# M503X.net
KiCad netlist of a schematic drawn in EAGLE
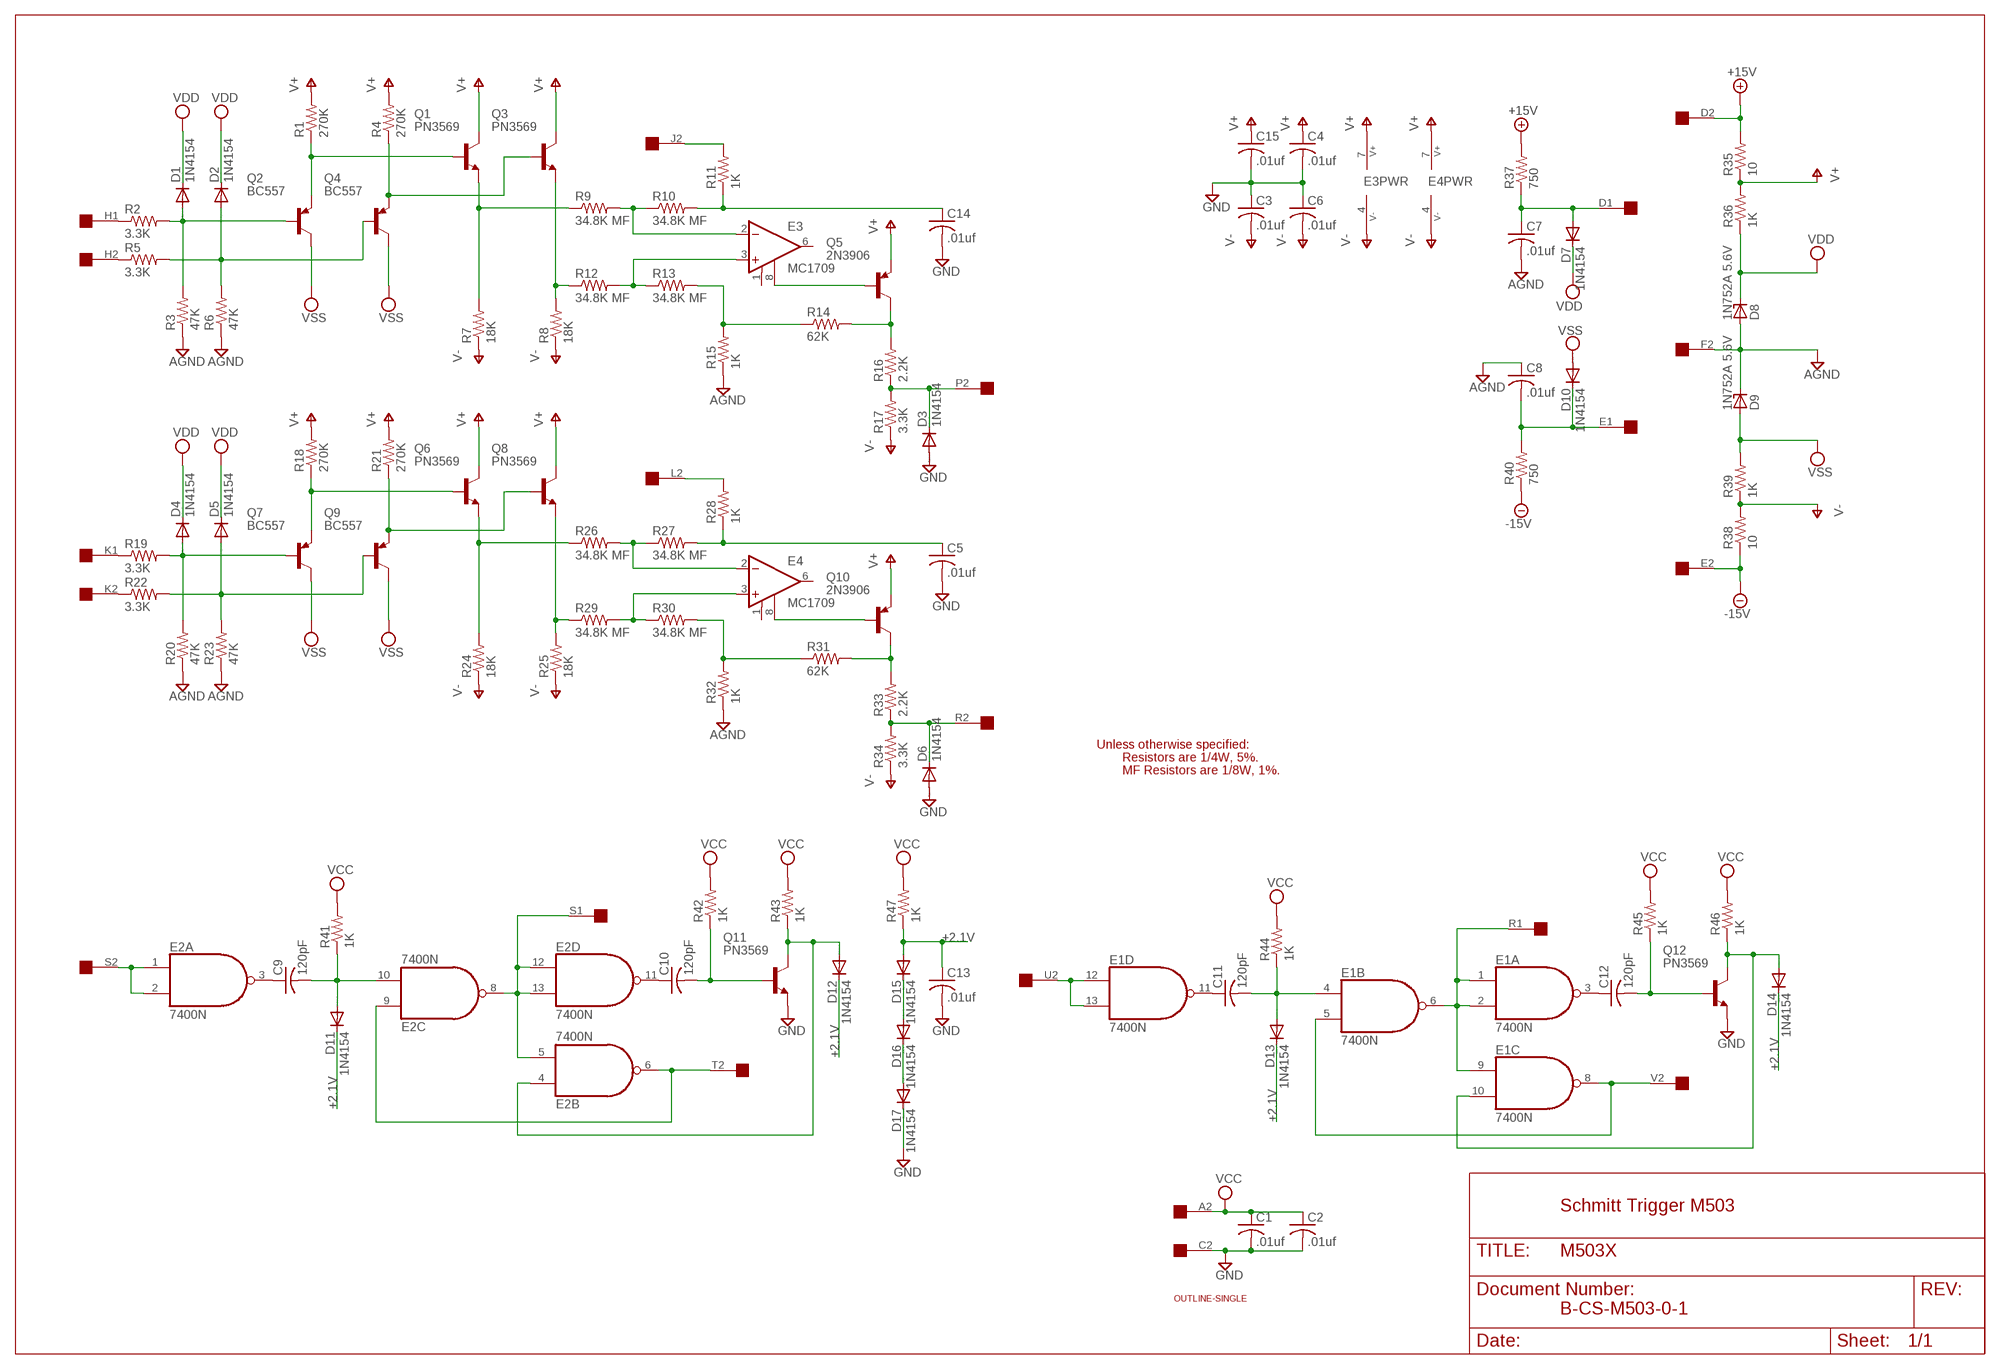
[diagram p0: schematic, sheet 1]

(export (version "E")
  (design (tool "Eeschema 10.0.6"))
  (components
    (comp (ref "C1")
      (value ".01uf")
      (footprint "eagle-import:C075-032X103")
      (libsource (lib "eagle-import") (part "C-US075-032X103"))
    )
    (comp (ref "C2")
      (value ".01uf")
      (footprint "eagle-import:C075-032X103")
      (libsource (lib "eagle-import") (part "C-US075-032X103"))
    )
    (comp (ref "C3")
      (value ".01uf")
      (footprint "eagle-import:C050-025X075")
      (libsource (lib "eagle-import") (part "C-US050-025X075"))
    )
    (comp (ref "C4")
      (value ".01uf")
      (footprint "eagle-import:C050-025X075")
      (libsource (lib "eagle-import") (part "C-US050-025X075"))
    )
    (comp (ref "C5")
      (value ".01uf")
      (footprint "eagle-import:C050-025X075")
      (libsource (lib "eagle-import") (part "C-US050-025X075"))
    )
    (comp (ref "C6")
      (value ".01uf")
      (footprint "eagle-import:C050-025X075")
      (libsource (lib "eagle-import") (part "C-US050-025X075"))
    )
    (comp (ref "C7")
      (value ".01uf")
      (footprint "eagle-import:C050-025X075")
      (libsource (lib "eagle-import") (part "C-US050-025X075"))
    )
    (comp (ref "C8")
      (value ".01uf")
      (footprint "eagle-import:C050-025X075")
      (libsource (lib "eagle-import") (part "C-US050-025X075"))
    )
    (comp (ref "C9")
      (value "120pF")
      (footprint "eagle-import:C050-025X075")
      (libsource (lib "eagle-import") (part "C-US050-025X075"))
    )
    (comp (ref "C10")
      (value "120pF")
      (footprint "eagle-import:C050-025X075")
      (libsource (lib "eagle-import") (part "C-US050-025X075"))
    )
    (comp (ref "C11")
      (value "120pF")
      (footprint "eagle-import:C050-025X075")
      (libsource (lib "eagle-import") (part "C-US050-025X075"))
    )
    (comp (ref "C12")
      (value "120pF")
      (footprint "eagle-import:C050-025X075")
      (libsource (lib "eagle-import") (part "C-US050-025X075"))
    )
    (comp (ref "C13")
      (value ".01uf")
      (footprint "eagle-import:C050-025X075")
      (libsource (lib "eagle-import") (part "C-US050-025X075"))
    )
    (comp (ref "C14")
      (value ".01uf")
      (footprint "eagle-import:C050-025X075")
      (libsource (lib "eagle-import") (part "C-US050-025X075"))
    )
    (comp (ref "C15")
      (value ".01uf")
      (footprint "eagle-import:C050-025X075")
      (libsource (lib "eagle-import") (part "C-US050-025X075"))
    )
    (comp (ref "D1")
      (value "1N4154")
      (footprint "eagle-import:DO35-10")
      (libsource (lib "eagle-import") (part "1N4148DO35-10"))
    )
    (comp (ref "D2")
      (value "1N4154")
      (footprint "eagle-import:DO35-10")
      (libsource (lib "eagle-import") (part "1N4148DO35-10"))
    )
    (comp (ref "D3")
      (value "1N4154")
      (footprint "eagle-import:DO35-10")
      (libsource (lib "eagle-import") (part "1N4148DO35-10"))
    )
    (comp (ref "D4")
      (value "1N4154")
      (footprint "eagle-import:DO35-10")
      (libsource (lib "eagle-import") (part "1N4148DO35-10"))
    )
    (comp (ref "D5")
      (value "1N4154")
      (footprint "eagle-import:DO35-10")
      (libsource (lib "eagle-import") (part "1N4148DO35-10"))
    )
    (comp (ref "D6")
      (value "1N4154")
      (footprint "eagle-import:DO35-10")
      (libsource (lib "eagle-import") (part "1N4148DO35-10"))
    )
    (comp (ref "D7")
      (value "1N4154")
      (footprint "eagle-import:DO35-10")
      (libsource (lib "eagle-import") (part "1N4148DO35-10"))
    )
    (comp (ref "D8")
      (value "1N752A 5.6V")
      (footprint "eagle-import:DO35Z10")
      (libsource (lib "eagle-import") (part "ZENER-DIODEDO35Z10"))
    )
    (comp (ref "D9")
      (value "1N752A 5.6V")
      (footprint "eagle-import:DO35Z10")
      (libsource (lib "eagle-import") (part "ZENER-DIODEDO35Z10"))
    )
    (comp (ref "D10")
      (value "1N4154")
      (footprint "eagle-import:DO35-10")
      (libsource (lib "eagle-import") (part "1N4148DO35-10"))
    )
    (comp (ref "D11")
      (value "1N4154")
      (footprint "eagle-import:DO35-10")
      (libsource (lib "eagle-import") (part "1N4148DO35-10"))
    )
    (comp (ref "D12")
      (value "1N4154")
      (footprint "eagle-import:DO35-10")
      (libsource (lib "eagle-import") (part "1N4148DO35-10"))
    )
    (comp (ref "D13")
      (value "1N4154")
      (footprint "eagle-import:DO35-10")
      (libsource (lib "eagle-import") (part "1N4148DO35-10"))
    )
    (comp (ref "D14")
      (value "1N4154")
      (footprint "eagle-import:DO35-10")
      (libsource (lib "eagle-import") (part "1N4148DO35-10"))
    )
    (comp (ref "D15")
      (value "1N4154")
      (footprint "eagle-import:DO35-10")
      (libsource (lib "eagle-import") (part "1N4148DO35-10"))
    )
    (comp (ref "D16")
      (value "1N4154")
      (footprint "eagle-import:DO35-10")
      (libsource (lib "eagle-import") (part "1N4148DO35-10"))
    )
    (comp (ref "D17")
      (value "1N4154")
      (footprint "eagle-import:DO35-10")
      (libsource (lib "eagle-import") (part "1N4148DO35-10"))
    )
    (comp (ref "E1")
      (value "7400N")
      (footprint "eagle-import:DIL14")
      (libsource (lib "eagle-import") (part "7400N"))
    )
    (comp (ref "E2")
      (value "7400N")
      (footprint "eagle-import:DIL14")
      (libsource (lib "eagle-import") (part "7400N"))
    )
    (comp (ref "E3")
      (value "MC1709")
      (footprint "eagle-import:TO99C")
      (libsource (lib "eagle-import") (part "LM301C"))
    )
    (comp (ref "E4")
      (value "MC1709")
      (footprint "eagle-import:TO99B")
      (libsource (lib "eagle-import") (part "LM301B"))
    )
    (comp (ref "Q1")
      (value "PN3569")
      (footprint "eagle-import:TO39")
      (libsource (lib "eagle-import") (part "2N3019"))
    )
    (comp (ref "Q2")
      (value "BC557")
      (footprint "eagle-import:TO39")
      (libsource (lib "eagle-import") (part "2N2904"))
    )
    (comp (ref "Q3")
      (value "PN3569")
      (footprint "eagle-import:TO39")
      (libsource (lib "eagle-import") (part "2N3019"))
    )
    (comp (ref "Q4")
      (value "BC557")
      (footprint "eagle-import:TO39")
      (libsource (lib "eagle-import") (part "2N2904"))
    )
    (comp (ref "Q5")
      (value "2N3906")
      (footprint "eagle-import:TO39")
      (libsource (lib "eagle-import") (part "2N2904"))
    )
    (comp (ref "Q6")
      (value "PN3569")
      (footprint "eagle-import:TO39")
      (libsource (lib "eagle-import") (part "2N3019"))
    )
    (comp (ref "Q7")
      (value "BC557")
      (footprint "eagle-import:TO39")
      (libsource (lib "eagle-import") (part "2N2904"))
    )
    (comp (ref "Q8")
      (value "PN3569")
      (footprint "eagle-import:TO39")
      (libsource (lib "eagle-import") (part "2N3019"))
    )
    (comp (ref "Q9")
      (value "BC557")
      (footprint "eagle-import:TO39")
      (libsource (lib "eagle-import") (part "2N2904"))
    )
    (comp (ref "Q10")
      (value "2N3906")
      (footprint "eagle-import:TO39")
      (libsource (lib "eagle-import") (part "2N2904"))
    )
    (comp (ref "Q11")
      (value "PN3569")
      (footprint "eagle-import:TO39")
      (libsource (lib "eagle-import") (part "2N3019"))
    )
    (comp (ref "Q12")
      (value "PN3569")
      (footprint "eagle-import:TO39")
      (libsource (lib "eagle-import") (part "2N3019"))
    )
    (comp (ref "R1")
      (value "270K")
      (footprint "eagle-import:0207_10")
      (libsource (lib "eagle-import") (part "R-US_0207/10"))
    )
    (comp (ref "R2")
      (value "3.3K")
      (footprint "eagle-import:0207_10")
      (libsource (lib "eagle-import") (part "R-US_0207/10"))
    )
    (comp (ref "R3")
      (value "47K")
      (footprint "eagle-import:0207_10")
      (libsource (lib "eagle-import") (part "R-US_0207/10"))
    )
    (comp (ref "R4")
      (value "270K")
      (footprint "eagle-import:0207_10")
      (libsource (lib "eagle-import") (part "R-US_0207/10"))
    )
    (comp (ref "R5")
      (value "3.3K")
      (footprint "eagle-import:0207_10")
      (libsource (lib "eagle-import") (part "R-US_0207/10"))
    )
    (comp (ref "R6")
      (value "47K")
      (footprint "eagle-import:0207_10")
      (libsource (lib "eagle-import") (part "R-US_0207/10"))
    )
    (comp (ref "R7")
      (value "18K")
      (footprint "eagle-import:0207_10")
      (libsource (lib "eagle-import") (part "R-US_0207/10"))
    )
    (comp (ref "R8")
      (value "18K")
      (footprint "eagle-import:0207_10")
      (libsource (lib "eagle-import") (part "R-US_0207/10"))
    )
    (comp (ref "R9")
      (value "34.8K MF")
      (footprint "eagle-import:0207_10")
      (libsource (lib "eagle-import") (part "R-US_0207/10"))
    )
    (comp (ref "R10")
      (value "34.8K MF")
      (footprint "eagle-import:0207_10")
      (libsource (lib "eagle-import") (part "R-US_0207/10"))
    )
    (comp (ref "R11")
      (value "1K")
      (footprint "eagle-import:0207_10")
      (libsource (lib "eagle-import") (part "R-US_0207/10"))
    )
    (comp (ref "R12")
      (value "34.8K MF")
      (footprint "eagle-import:0207_10")
      (libsource (lib "eagle-import") (part "R-US_0207/10"))
    )
    (comp (ref "R13")
      (value "34.8K MF")
      (footprint "eagle-import:0207_10")
      (libsource (lib "eagle-import") (part "R-US_0207/10"))
    )
    (comp (ref "R14")
      (value "62K")
      (footprint "eagle-import:0207_10")
      (libsource (lib "eagle-import") (part "R-US_0207/10"))
    )
    (comp (ref "R15")
      (value "1K")
      (footprint "eagle-import:0207_10")
      (libsource (lib "eagle-import") (part "R-US_0207/10"))
    )
    (comp (ref "R16")
      (value "2.2K")
      (footprint "eagle-import:0207_10")
      (libsource (lib "eagle-import") (part "R-US_0207/10"))
    )
    (comp (ref "R17")
      (value "3.3K")
      (footprint "eagle-import:0207_10")
      (libsource (lib "eagle-import") (part "R-US_0207/10"))
    )
    (comp (ref "R18")
      (value "270K")
      (footprint "eagle-import:0207_10")
      (libsource (lib "eagle-import") (part "R-US_0207/10"))
    )
    (comp (ref "R19")
      (value "3.3K")
      (footprint "eagle-import:0207_10")
      (libsource (lib "eagle-import") (part "R-US_0207/10"))
    )
    (comp (ref "R20")
      (value "47K")
      (footprint "eagle-import:0207_10")
      (libsource (lib "eagle-import") (part "R-US_0207/10"))
    )
    (comp (ref "R21")
      (value "270K")
      (footprint "eagle-import:0207_10")
      (libsource (lib "eagle-import") (part "R-US_0207/10"))
    )
    (comp (ref "R22")
      (value "3.3K")
      (footprint "eagle-import:0207_10")
      (libsource (lib "eagle-import") (part "R-US_0207/10"))
    )
    (comp (ref "R23")
      (value "47K")
      (footprint "eagle-import:0207_10")
      (libsource (lib "eagle-import") (part "R-US_0207/10"))
    )
    (comp (ref "R24")
      (value "18K")
      (footprint "eagle-import:0207_10")
      (libsource (lib "eagle-import") (part "R-US_0207/10"))
    )
    (comp (ref "R25")
      (value "18K")
      (footprint "eagle-import:0207_10")
      (libsource (lib "eagle-import") (part "R-US_0207/10"))
    )
    (comp (ref "R26")
      (value "34.8K MF")
      (footprint "eagle-import:0207_10")
      (libsource (lib "eagle-import") (part "R-US_0207/10"))
    )
    (comp (ref "R27")
      (value "34.8K MF")
      (footprint "eagle-import:0207_10")
      (libsource (lib "eagle-import") (part "R-US_0207/10"))
    )
    (comp (ref "R28")
      (value "1K")
      (footprint "eagle-import:0207_10")
      (libsource (lib "eagle-import") (part "R-US_0207/10"))
    )
    (comp (ref "R29")
      (value "34.8K MF")
      (footprint "eagle-import:0207_10")
      (libsource (lib "eagle-import") (part "R-US_0207/10"))
    )
    (comp (ref "R30")
      (value "34.8K MF")
      (footprint "eagle-import:0207_10")
      (libsource (lib "eagle-import") (part "R-US_0207/10"))
    )
    (comp (ref "R31")
      (value "62K")
      (footprint "eagle-import:0207_10")
      (libsource (lib "eagle-import") (part "R-US_0207/10"))
    )
    (comp (ref "R32")
      (value "1K")
      (footprint "eagle-import:0207_10")
      (libsource (lib "eagle-import") (part "R-US_0207/10"))
    )
    (comp (ref "R33")
      (value "2.2K")
      (footprint "eagle-import:0207_10")
      (libsource (lib "eagle-import") (part "R-US_0207/10"))
    )
    (comp (ref "R34")
      (value "3.3K")
      (footprint "eagle-import:0207_10")
      (libsource (lib "eagle-import") (part "R-US_0207/10"))
    )
    (comp (ref "R35")
      (value "10")
      (footprint "eagle-import:0207_10")
      (libsource (lib "eagle-import") (part "R-US_0207/10"))
    )
    (comp (ref "R36")
      (value "1K")
      (footprint "eagle-import:0207_10")
      (libsource (lib "eagle-import") (part "R-US_0207/10"))
    )
    (comp (ref "R37")
      (value "750")
      (footprint "eagle-import:0207_10")
      (libsource (lib "eagle-import") (part "R-US_0207/10"))
    )
    (comp (ref "R38")
      (value "10")
      (footprint "eagle-import:0207_10")
      (libsource (lib "eagle-import") (part "R-US_0207/10"))
    )
    (comp (ref "R39")
      (value "1K")
      (footprint "eagle-import:0207_10")
      (libsource (lib "eagle-import") (part "R-US_0207/10"))
    )
    (comp (ref "R40")
      (value "750")
      (footprint "eagle-import:0207_10")
      (libsource (lib "eagle-import") (part "R-US_0207/10"))
    )
    (comp (ref "R41")
      (value "1K")
      (footprint "eagle-import:0207_10")
      (libsource (lib "eagle-import") (part "R-US_0207/10"))
    )
    (comp (ref "R42")
      (value "1K")
      (footprint "eagle-import:0207_10")
      (libsource (lib "eagle-import") (part "R-US_0207/10"))
    )
    (comp (ref "R43")
      (value "1K")
      (footprint "eagle-import:0207_10")
      (libsource (lib "eagle-import") (part "R-US_0207/10"))
    )
    (comp (ref "R44")
      (value "1K")
      (footprint "eagle-import:0207_10")
      (libsource (lib "eagle-import") (part "R-US_0207/10"))
    )
    (comp (ref "R45")
      (value "1K")
      (footprint "eagle-import:0207_10")
      (libsource (lib "eagle-import") (part "R-US_0207/10"))
    )
    (comp (ref "R46")
      (value "1K")
      (footprint "eagle-import:0207_10")
      (libsource (lib "eagle-import") (part "R-US_0207/10"))
    )
    (comp (ref "R47")
      (value "1K")
      (footprint "eagle-import:0207_10")
      (libsource (lib "eagle-import") (part "R-US_0207/10"))
    )
    (comp (ref "U$2")
      (value "SINGLE")
      (footprint "eagle-import:EDGE-CON2")
      (libsource (lib "eagle-import") (part "SINGLE"))
    )
    (comp (ref "U$4")
      (value "OUTLINE-SINGLE")
      (footprint "eagle-import:SINGLE")
      (libsource (lib "eagle-import") (part "OUTLINE-SINGLE"))
    )
  )
  (nets
    (net (code "1") (name "+15V") (class "Default")
      (node (ref "R35") (pin "2") (pinfunction "2_2") (pintype "passive"))
      (node (ref "R37") (pin "2") (pinfunction "2_2") (pintype "passive"))
      (node (ref "U$2") (pin "D2") (pinfunction "1_D2") (pintype "bidirectional"))
    )
    (net (code "2") (name "-15V") (class "Default")
      (node (ref "R38") (pin "1") (pinfunction "1_1") (pintype "passive"))
      (node (ref "R40") (pin "1") (pinfunction "1_1") (pintype "passive"))
      (node (ref "U$2") (pin "E2") (pinfunction "1_E2") (pintype "bidirectional"))
    )
    (net (code "3") (name "/+2.1V") (class "Default")
      (node (ref "C13") (pin "1") (pinfunction "1_1") (pintype "passive"))
      (node (ref "D11") (pin "C") (pinfunction "C_C") (pintype "passive"))
      (node (ref "D12") (pin "C") (pinfunction "C_C") (pintype "passive"))
      (node (ref "D13") (pin "C") (pinfunction "C_C") (pintype "passive"))
      (node (ref "D14") (pin "C") (pinfunction "C_C") (pintype "passive"))
      (node (ref "D15") (pin "A") (pinfunction "A_A") (pintype "passive"))
      (node (ref "R47") (pin "1") (pinfunction "1_1") (pintype "passive"))
    )
    (net (code "4") (name "AGND") (class "Default")
      (node (ref "C7") (pin "2") (pinfunction "2_2") (pintype "passive"))
      (node (ref "C8") (pin "1") (pinfunction "1_1") (pintype "passive"))
      (node (ref "D8") (pin "A") (pinfunction "A_A") (pintype "passive"))
      (node (ref "D9") (pin "C") (pinfunction "C_C") (pintype "passive"))
      (node (ref "R15") (pin "1") (pinfunction "1_1") (pintype "passive"))
      (node (ref "R20") (pin "1") (pinfunction "1_1") (pintype "passive"))
      (node (ref "R23") (pin "1") (pinfunction "1_1") (pintype "passive"))
      (node (ref "R3") (pin "1") (pinfunction "1_1") (pintype "passive"))
      (node (ref "R32") (pin "1") (pinfunction "1_1") (pintype "passive"))
      (node (ref "R6") (pin "1") (pinfunction "1_1") (pintype "passive"))
      (node (ref "U$2") (pin "F2") (pinfunction "1_F2") (pintype "bidirectional"))
    )
    (net (code "5") (name "GND") (class "Default")
      (node (ref "C1") (pin "2") (pinfunction "2_2") (pintype "passive"))
      (node (ref "C13") (pin "2") (pinfunction "2_2") (pintype "passive"))
      (node (ref "C14") (pin "2") (pinfunction "2_2") (pintype "passive"))
      (node (ref "C15") (pin "2") (pinfunction "2_2") (pintype "passive"))
      (node (ref "C2") (pin "2") (pinfunction "2_2") (pintype "passive"))
      (node (ref "C3") (pin "1") (pinfunction "1_1") (pintype "passive"))
      (node (ref "C4") (pin "2") (pinfunction "2_2") (pintype "passive"))
      (node (ref "C5") (pin "2") (pinfunction "2_2") (pintype "passive"))
      (node (ref "C6") (pin "1") (pinfunction "1_1") (pintype "passive"))
      (node (ref "D17") (pin "C") (pinfunction "C_C") (pintype "passive"))
      (node (ref "D3") (pin "A") (pinfunction "A_A") (pintype "passive"))
      (node (ref "D6") (pin "A") (pinfunction "A_A") (pintype "passive"))
      (node (ref "Q11") (pin "1") (pinfunction "E_1") (pintype "passive"))
      (node (ref "Q12") (pin "1") (pinfunction "E_1") (pintype "passive"))
      (node (ref "U$2") (pin "C2") (pinfunction "1_C2") (pintype "bidirectional"))
    )
    (net (code "6") (name "Net-(C5-Pad1)") (class "Default")
      (node (ref "C5") (pin "1") (pinfunction "1_1") (pintype "passive"))
      (node (ref "R27") (pin "2") (pinfunction "2_2") (pintype "passive"))
      (node (ref "R28") (pin "1") (pinfunction "1_1") (pintype "passive"))
    )
    (net (code "7") (name "Net-(C14-Pad1)") (class "Default")
      (node (ref "C14") (pin "1") (pinfunction "1_1") (pintype "passive"))
      (node (ref "R10") (pin "2") (pinfunction "2_2") (pintype "passive"))
      (node (ref "R11") (pin "1") (pinfunction "1_1") (pintype "passive"))
    )
    (net (code "8") (name "Net-(D15-PadC)") (class "Default")
      (node (ref "D15") (pin "C") (pinfunction "C_C") (pintype "passive"))
      (node (ref "D16") (pin "A") (pinfunction "A_A") (pintype "passive"))
    )
    (net (code "9") (name "Net-(D16-PadC)") (class "Default")
      (node (ref "D16") (pin "C") (pinfunction "C_C") (pintype "passive"))
      (node (ref "D17") (pin "A") (pinfunction "A_A") (pintype "passive"))
    )
    (net (code "10") (name "Net-(E1A-I0)") (class "Default")
      (node (ref "E1") (pin "1") (pinfunction "I0_1") (pintype "input"))
      (node (ref "E1") (pin "2") (pinfunction "I1_2") (pintype "input"))
      (node (ref "E1") (pin "6") (pinfunction "O_6") (pintype "output"))
      (node (ref "E1") (pin "9") (pinfunction "I0_9") (pintype "input"))
      (node (ref "U$2") (pin "R1") (pinfunction "1_R1") (pintype "bidirectional"))
    )
    (net (code "11") (name "Net-(E1A-O)") (class "Default")
      (node (ref "C12") (pin "1") (pinfunction "1_1") (pintype "passive"))
      (node (ref "E1") (pin "3") (pinfunction "O_3") (pintype "output"))
    )
    (net (code "12") (name "Net-(E1B-I0)") (class "Default")
      (node (ref "C11") (pin "2") (pinfunction "2_2") (pintype "passive"))
      (node (ref "D13") (pin "A") (pinfunction "A_A") (pintype "passive"))
      (node (ref "E1") (pin "4") (pinfunction "I0_4") (pintype "input"))
      (node (ref "R44") (pin "1") (pinfunction "1_1") (pintype "passive"))
    )
    (net (code "13") (name "Net-(E1B-I1)") (class "Default")
      (node (ref "E1") (pin "5") (pinfunction "I1_5") (pintype "input"))
      (node (ref "E1") (pin "8") (pinfunction "O_8") (pintype "output"))
      (node (ref "U$2") (pin "V2") (pinfunction "1_V2") (pintype "bidirectional"))
    )
    (net (code "14") (name "Net-(E1C-I1)") (class "Default")
      (node (ref "D14") (pin "A") (pinfunction "A_A") (pintype "passive"))
      (node (ref "E1") (pin "10") (pinfunction "I1_10") (pintype "input"))
      (node (ref "Q12") (pin "3") (pinfunction "C_3") (pintype "passive"))
      (node (ref "R46") (pin "1") (pinfunction "1_1") (pintype "passive"))
    )
    (net (code "15") (name "Net-(E1D-I0)") (class "Default")
      (node (ref "E1") (pin "12") (pinfunction "I0_12") (pintype "input"))
      (node (ref "E1") (pin "13") (pinfunction "I1_13") (pintype "input"))
      (node (ref "U$2") (pin "U2") (pinfunction "1_U2") (pintype "bidirectional"))
    )
    (net (code "16") (name "Net-(E1D-O)") (class "Default")
      (node (ref "C11") (pin "1") (pinfunction "1_1") (pintype "passive"))
      (node (ref "E1") (pin "11") (pinfunction "O_11") (pintype "output"))
    )
    (net (code "17") (name "Net-(E2A-I0)") (class "Default")
      (node (ref "E2") (pin "1") (pinfunction "I0_1") (pintype "input"))
      (node (ref "E2") (pin "2") (pinfunction "I1_2") (pintype "input"))
      (node (ref "U$2") (pin "S2") (pinfunction "1_S2") (pintype "bidirectional"))
    )
    (net (code "18") (name "Net-(E2A-O)") (class "Default")
      (node (ref "C9") (pin "1") (pinfunction "1_1") (pintype "passive"))
      (node (ref "E2") (pin "3") (pinfunction "O_3") (pintype "output"))
    )
    (net (code "19") (name "Net-(E2B-I0)") (class "Default")
      (node (ref "D12") (pin "A") (pinfunction "A_A") (pintype "passive"))
      (node (ref "E2") (pin "4") (pinfunction "I0_4") (pintype "input"))
      (node (ref "Q11") (pin "3") (pinfunction "C_3") (pintype "passive"))
      (node (ref "R43") (pin "1") (pinfunction "1_1") (pintype "passive"))
    )
    (net (code "20") (name "Net-(E2B-I1)") (class "Default")
      (node (ref "E2") (pin "12") (pinfunction "I0_12") (pintype "input"))
      (node (ref "E2") (pin "13") (pinfunction "I1_13") (pintype "input"))
      (node (ref "E2") (pin "5") (pinfunction "I1_5") (pintype "input"))
      (node (ref "E2") (pin "8") (pinfunction "O_8") (pintype "output"))
      (node (ref "U$2") (pin "S1") (pinfunction "1_S1") (pintype "bidirectional"))
    )
    (net (code "21") (name "Net-(E2B-O)") (class "Default")
      (node (ref "E2") (pin "6") (pinfunction "O_6") (pintype "output"))
      (node (ref "E2") (pin "9") (pinfunction "I0_9") (pintype "input"))
      (node (ref "U$2") (pin "T2") (pinfunction "1_T2") (pintype "bidirectional"))
    )
    (net (code "22") (name "Net-(E2C-I1)") (class "Default")
      (node (ref "C9") (pin "2") (pinfunction "2_2") (pintype "passive"))
      (node (ref "D11") (pin "A") (pinfunction "A_A") (pintype "passive"))
      (node (ref "E2") (pin "10") (pinfunction "I1_10") (pintype "input"))
      (node (ref "R41") (pin "1") (pinfunction "1_1") (pintype "passive"))
    )
    (net (code "23") (name "Net-(E2D-O)") (class "Default")
      (node (ref "C10") (pin "1") (pinfunction "1_1") (pintype "passive"))
      (node (ref "E2") (pin "11") (pinfunction "O_11") (pintype "output"))
    )
    (net (code "24") (name "Net-(E3A-+IN)") (class "Default")
      (node (ref "E3") (pin "3") (pinfunction "+IN_3") (pintype "input"))
      (node (ref "R12") (pin "2") (pinfunction "2_2") (pintype "passive"))
      (node (ref "R13") (pin "1") (pinfunction "1_1") (pintype "passive"))
    )
    (net (code "25") (name "Net-(E3A--IN)") (class "Default")
      (node (ref "E3") (pin "2") (pinfunction "-IN_2") (pintype "input"))
      (node (ref "R10") (pin "1") (pinfunction "1_1") (pintype "passive"))
      (node (ref "R9") (pin "2") (pinfunction "2_2") (pintype "passive"))
    )
    (net (code "26") (name "Net-(E3A-CMP)") (class "Default")
      (node (ref "E3") (pin "8") (pinfunction "CMP_8") (pintype "passive"))
      (node (ref "Q5") (pin "2") (pinfunction "B_2") (pintype "passive"))
    )
    (net (code "27") (name "Net-(E4A-+IN)") (class "Default")
      (node (ref "E4") (pin "3") (pinfunction "+IN_3") (pintype "input"))
      (node (ref "R29") (pin "2") (pinfunction "2_2") (pintype "passive"))
      (node (ref "R30") (pin "1") (pinfunction "1_1") (pintype "passive"))
    )
    (net (code "28") (name "Net-(E4A--IN)") (class "Default")
      (node (ref "E4") (pin "2") (pinfunction "-IN_2") (pintype "input"))
      (node (ref "R26") (pin "2") (pinfunction "2_2") (pintype "passive"))
      (node (ref "R27") (pin "1") (pinfunction "1_1") (pintype "passive"))
    )
    (net (code "29") (name "Net-(E4A-CMP)") (class "Default")
      (node (ref "E4") (pin "8") (pinfunction "CMP_8") (pintype "passive"))
      (node (ref "Q10") (pin "2") (pinfunction "B_2") (pintype "passive"))
    )
    (net (code "30") (name "Net-(Q1-B)") (class "Default")
      (node (ref "Q1") (pin "2") (pinfunction "B_2") (pintype "passive"))
      (node (ref "Q2") (pin "1") (pinfunction "E_1") (pintype "passive"))
      (node (ref "R1") (pin "1") (pinfunction "1_1") (pintype "passive"))
    )
    (net (code "31") (name "Net-(Q1-E)") (class "Default")
      (node (ref "Q1") (pin "1") (pinfunction "E_1") (pintype "passive"))
      (node (ref "R7") (pin "2") (pinfunction "2_2") (pintype "passive"))
      (node (ref "R9") (pin "1") (pinfunction "1_1") (pintype "passive"))
    )
    (net (code "32") (name "Net-(Q2-B)") (class "Default")
      (node (ref "D1") (pin "A") (pinfunction "A_A") (pintype "passive"))
      (node (ref "Q2") (pin "2") (pinfunction "B_2") (pintype "passive"))
      (node (ref "R2") (pin "2") (pinfunction "2_2") (pintype "passive"))
      (node (ref "R3") (pin "2") (pinfunction "2_2") (pintype "passive"))
    )
    (net (code "33") (name "Net-(Q3-B)") (class "Default")
      (node (ref "Q3") (pin "2") (pinfunction "B_2") (pintype "passive"))
      (node (ref "Q4") (pin "1") (pinfunction "E_1") (pintype "passive"))
      (node (ref "R4") (pin "1") (pinfunction "1_1") (pintype "passive"))
    )
    (net (code "34") (name "Net-(Q3-E)") (class "Default")
      (node (ref "Q3") (pin "1") (pinfunction "E_1") (pintype "passive"))
      (node (ref "R12") (pin "1") (pinfunction "1_1") (pintype "passive"))
      (node (ref "R8") (pin "2") (pinfunction "2_2") (pintype "passive"))
    )
    (net (code "35") (name "Net-(Q4-B)") (class "Default")
      (node (ref "D2") (pin "A") (pinfunction "A_A") (pintype "passive"))
      (node (ref "Q4") (pin "2") (pinfunction "B_2") (pintype "passive"))
      (node (ref "R5") (pin "2") (pinfunction "2_2") (pintype "passive"))
      (node (ref "R6") (pin "2") (pinfunction "2_2") (pintype "passive"))
    )
    (net (code "36") (name "Net-(Q5-C)") (class "Default")
      (node (ref "Q5") (pin "3") (pinfunction "C_3") (pintype "passive"))
      (node (ref "R14") (pin "2") (pinfunction "2_2") (pintype "passive"))
      (node (ref "R16") (pin "2") (pinfunction "2_2") (pintype "passive"))
    )
    (net (code "37") (name "Net-(Q6-B)") (class "Default")
      (node (ref "Q6") (pin "2") (pinfunction "B_2") (pintype "passive"))
      (node (ref "Q7") (pin "1") (pinfunction "E_1") (pintype "passive"))
      (node (ref "R18") (pin "1") (pinfunction "1_1") (pintype "passive"))
    )
    (net (code "38") (name "Net-(Q6-E)") (class "Default")
      (node (ref "Q6") (pin "1") (pinfunction "E_1") (pintype "passive"))
      (node (ref "R24") (pin "2") (pinfunction "2_2") (pintype "passive"))
      (node (ref "R26") (pin "1") (pinfunction "1_1") (pintype "passive"))
    )
    (net (code "39") (name "Net-(Q7-B)") (class "Default")
      (node (ref "D4") (pin "A") (pinfunction "A_A") (pintype "passive"))
      (node (ref "Q7") (pin "2") (pinfunction "B_2") (pintype "passive"))
      (node (ref "R19") (pin "2") (pinfunction "2_2") (pintype "passive"))
      (node (ref "R20") (pin "2") (pinfunction "2_2") (pintype "passive"))
    )
    (net (code "40") (name "Net-(Q8-B)") (class "Default")
      (node (ref "Q8") (pin "2") (pinfunction "B_2") (pintype "passive"))
      (node (ref "Q9") (pin "1") (pinfunction "E_1") (pintype "passive"))
      (node (ref "R21") (pin "1") (pinfunction "1_1") (pintype "passive"))
    )
    (net (code "41") (name "Net-(Q8-E)") (class "Default")
      (node (ref "Q8") (pin "1") (pinfunction "E_1") (pintype "passive"))
      (node (ref "R25") (pin "2") (pinfunction "2_2") (pintype "passive"))
      (node (ref "R29") (pin "1") (pinfunction "1_1") (pintype "passive"))
    )
    (net (code "42") (name "Net-(Q9-B)") (class "Default")
      (node (ref "D5") (pin "A") (pinfunction "A_A") (pintype "passive"))
      (node (ref "Q9") (pin "2") (pinfunction "B_2") (pintype "passive"))
      (node (ref "R22") (pin "2") (pinfunction "2_2") (pintype "passive"))
      (node (ref "R23") (pin "2") (pinfunction "2_2") (pintype "passive"))
    )
    (net (code "43") (name "Net-(Q10-C)") (class "Default")
      (node (ref "Q10") (pin "3") (pinfunction "C_3") (pintype "passive"))
      (node (ref "R31") (pin "2") (pinfunction "2_2") (pintype "passive"))
      (node (ref "R33") (pin "2") (pinfunction "2_2") (pintype "passive"))
    )
    (net (code "44") (name "Net-(Q11-B)") (class "Default")
      (node (ref "C10") (pin "2") (pinfunction "2_2") (pintype "passive"))
      (node (ref "Q11") (pin "2") (pinfunction "B_2") (pintype "passive"))
      (node (ref "R42") (pin "1") (pinfunction "1_1") (pintype "passive"))
    )
    (net (code "45") (name "Net-(Q12-B)") (class "Default")
      (node (ref "C12") (pin "2") (pinfunction "2_2") (pintype "passive"))
      (node (ref "Q12") (pin "2") (pinfunction "B_2") (pintype "passive"))
      (node (ref "R45") (pin "1") (pinfunction "1_1") (pintype "passive"))
    )
    (net (code "46") (name "Net-(R13-Pad2)") (class "Default")
      (node (ref "R13") (pin "2") (pinfunction "2_2") (pintype "passive"))
      (node (ref "R14") (pin "1") (pinfunction "1_1") (pintype "passive"))
      (node (ref "R15") (pin "2") (pinfunction "2_2") (pintype "passive"))
    )
    (net (code "47") (name "Net-(R30-Pad2)") (class "Default")
      (node (ref "R30") (pin "2") (pinfunction "2_2") (pintype "passive"))
      (node (ref "R31") (pin "1") (pinfunction "1_1") (pintype "passive"))
      (node (ref "R32") (pin "2") (pinfunction "2_2") (pintype "passive"))
    )
    (net (code "48") (name "Net-(U$2AB-1)") (class "Default")
      (node (ref "D6") (pin "C") (pinfunction "C_C") (pintype "passive"))
      (node (ref "R33") (pin "1") (pinfunction "1_1") (pintype "passive"))
      (node (ref "R34") (pin "2") (pinfunction "2_2") (pintype "passive"))
      (node (ref "U$2") (pin "R2") (pinfunction "1_R2") (pintype "bidirectional"))
    )
    (net (code "49") (name "Net-(U$2G-1)") (class "Default")
      (node (ref "C7") (pin "1") (pinfunction "1_1") (pintype "passive"))
      (node (ref "D7") (pin "A") (pinfunction "A_A") (pintype "passive"))
      (node (ref "R37") (pin "1") (pinfunction "1_1") (pintype "passive"))
      (node (ref "U$2") (pin "D1") (pinfunction "1_D1") (pintype "bidirectional"))
    )
    (net (code "50") (name "Net-(U$2I-1)") (class "Default")
      (node (ref "C8") (pin "2") (pinfunction "2_2") (pintype "passive"))
      (node (ref "D10") (pin "C") (pinfunction "C_C") (pintype "passive"))
      (node (ref "R40") (pin "2") (pinfunction "2_2") (pintype "passive"))
      (node (ref "U$2") (pin "E1") (pinfunction "1_E1") (pintype "bidirectional"))
    )
    (net (code "51") (name "Net-(U$2M-1)") (class "Default")
      (node (ref "R2") (pin "1") (pinfunction "1_1") (pintype "passive"))
      (node (ref "U$2") (pin "H1") (pinfunction "1_H1") (pintype "bidirectional"))
    )
    (net (code "52") (name "Net-(U$2N-1)") (class "Default")
      (node (ref "R5") (pin "1") (pinfunction "1_1") (pintype "passive"))
      (node (ref "U$2") (pin "H2") (pinfunction "1_H2") (pintype "bidirectional"))
    )
    (net (code "53") (name "Net-(U$2P-1)") (class "Default")
      (node (ref "R11") (pin "2") (pinfunction "2_2") (pintype "passive"))
      (node (ref "U$2") (pin "J2") (pinfunction "1_J2") (pintype "bidirectional"))
    )
    (net (code "54") (name "Net-(U$2Q-1)") (class "Default")
      (node (ref "R19") (pin "1") (pinfunction "1_1") (pintype "passive"))
      (node (ref "U$2") (pin "K1") (pinfunction "1_K1") (pintype "bidirectional"))
    )
    (net (code "55") (name "Net-(U$2R-1)") (class "Default")
      (node (ref "R22") (pin "1") (pinfunction "1_1") (pintype "passive"))
      (node (ref "U$2") (pin "K2") (pinfunction "1_K2") (pintype "bidirectional"))
    )
    (net (code "56") (name "Net-(U$2T-1)") (class "Default")
      (node (ref "R28") (pin "2") (pinfunction "2_2") (pintype "passive"))
      (node (ref "U$2") (pin "L2") (pinfunction "1_L2") (pintype "bidirectional"))
    )
    (net (code "57") (name "Net-(U$2Z-1)") (class "Default")
      (node (ref "D3") (pin "C") (pinfunction "C_C") (pintype "passive"))
      (node (ref "R16") (pin "1") (pinfunction "1_1") (pintype "passive"))
      (node (ref "R17") (pin "2") (pinfunction "2_2") (pintype "passive"))
      (node (ref "U$2") (pin "P2") (pinfunction "1_P2") (pintype "bidirectional"))
    )
    (net (code "58") (name "V+") (class "Default")
      (node (ref "C15") (pin "1") (pinfunction "1_1") (pintype "passive"))
      (node (ref "C4") (pin "1") (pinfunction "1_1") (pintype "passive"))
      (node (ref "E3") (pin "7") (pinfunction "+10V_7") (pintype "power_in"))
      (node (ref "E4") (pin "7") (pinfunction "+10V_7") (pintype "power_in"))
      (node (ref "Q1") (pin "3") (pinfunction "C_3") (pintype "passive"))
      (node (ref "Q10") (pin "1") (pinfunction "E_1") (pintype "passive"))
      (node (ref "Q3") (pin "3") (pinfunction "C_3") (pintype "passive"))
      (node (ref "Q5") (pin "1") (pinfunction "E_1") (pintype "passive"))
      (node (ref "Q6") (pin "3") (pinfunction "C_3") (pintype "passive"))
      (node (ref "Q8") (pin "3") (pinfunction "C_3") (pintype "passive"))
      (node (ref "R1") (pin "2") (pinfunction "2_2") (pintype "passive"))
      (node (ref "R18") (pin "2") (pinfunction "2_2") (pintype "passive"))
      (node (ref "R21") (pin "2") (pinfunction "2_2") (pintype "passive"))
      (node (ref "R35") (pin "1") (pinfunction "1_1") (pintype "passive"))
      (node (ref "R36") (pin "2") (pinfunction "2_2") (pintype "passive"))
      (node (ref "R4") (pin "2") (pinfunction "2_2") (pintype "passive"))
    )
    (net (code "59") (name "V-") (class "Default")
      (node (ref "C3") (pin "2") (pinfunction "2_2") (pintype "passive"))
      (node (ref "C6") (pin "2") (pinfunction "2_2") (pintype "passive"))
      (node (ref "E3") (pin "4") (pinfunction "-15V_4") (pintype "power_in"))
      (node (ref "E4") (pin "4") (pinfunction "-15V_4") (pintype "power_in"))
      (node (ref "R17") (pin "1") (pinfunction "1_1") (pintype "passive"))
      (node (ref "R24") (pin "1") (pinfunction "1_1") (pintype "passive"))
      (node (ref "R25") (pin "1") (pinfunction "1_1") (pintype "passive"))
      (node (ref "R34") (pin "1") (pinfunction "1_1") (pintype "passive"))
      (node (ref "R38") (pin "2") (pinfunction "2_2") (pintype "passive"))
      (node (ref "R39") (pin "1") (pinfunction "1_1") (pintype "passive"))
      (node (ref "R7") (pin "1") (pinfunction "1_1") (pintype "passive"))
      (node (ref "R8") (pin "1") (pinfunction "1_1") (pintype "passive"))
    )
    (net (code "60") (name "VCC") (class "Default")
      (node (ref "C1") (pin "1") (pinfunction "1_1") (pintype "passive"))
      (node (ref "C2") (pin "1") (pinfunction "1_1") (pintype "passive"))
      (node (ref "R41") (pin "2") (pinfunction "2_2") (pintype "passive"))
      (node (ref "R42") (pin "2") (pinfunction "2_2") (pintype "passive"))
      (node (ref "R43") (pin "2") (pinfunction "2_2") (pintype "passive"))
      (node (ref "R44") (pin "2") (pinfunction "2_2") (pintype "passive"))
      (node (ref "R45") (pin "2") (pinfunction "2_2") (pintype "passive"))
      (node (ref "R46") (pin "2") (pinfunction "2_2") (pintype "passive"))
      (node (ref "R47") (pin "2") (pinfunction "2_2") (pintype "passive"))
      (node (ref "U$2") (pin "A2") (pinfunction "1_A2") (pintype "bidirectional"))
    )
    (net (code "61") (name "VDD") (class "Default")
      (node (ref "D1") (pin "C") (pinfunction "C_C") (pintype "passive"))
      (node (ref "D2") (pin "C") (pinfunction "C_C") (pintype "passive"))
      (node (ref "D4") (pin "C") (pinfunction "C_C") (pintype "passive"))
      (node (ref "D5") (pin "C") (pinfunction "C_C") (pintype "passive"))
      (node (ref "D7") (pin "C") (pinfunction "C_C") (pintype "passive"))
      (node (ref "D8") (pin "C") (pinfunction "C_C") (pintype "passive"))
      (node (ref "R36") (pin "1") (pinfunction "1_1") (pintype "passive"))
    )
    (net (code "62") (name "VSS") (class "Default")
      (node (ref "D10") (pin "A") (pinfunction "A_A") (pintype "passive"))
      (node (ref "D9") (pin "A") (pinfunction "A_A") (pintype "passive"))
      (node (ref "Q2") (pin "3") (pinfunction "C_3") (pintype "passive"))
      (node (ref "Q4") (pin "3") (pinfunction "C_3") (pintype "passive"))
      (node (ref "Q7") (pin "3") (pinfunction "C_3") (pintype "passive"))
      (node (ref "Q9") (pin "3") (pinfunction "C_3") (pintype "passive"))
      (node (ref "R39") (pin "2") (pinfunction "2_2") (pintype "passive"))
    )
    (net (code "63") (name "unconnected-(E3A-ON{slash}CMP-Pad1)") (class "Default")
      (node (ref "E3") (pin "1") (pinfunction "ON/CMP_1") (pintype "passive"))
    )
    (net (code "64") (name "unconnected-(E3A-OUT-Pad6)") (class "Default")
      (node (ref "E3") (pin "6") (pinfunction "OUT_6") (pintype "output"))
    )
    (net (code "65") (name "unconnected-(E4A-ON{slash}CMP-Pad1)") (class "Default")
      (node (ref "E4") (pin "1") (pinfunction "ON/CMP_1") (pintype "passive"))
    )
    (net (code "66") (name "unconnected-(E4A-OUT-Pad6)") (class "Default")
      (node (ref "E4") (pin "6") (pinfunction "OUT_6") (pintype "output"))
    )
  )
)
